# 4-storage.net
KiCad netlist of a schematic drawn in Altium Designer
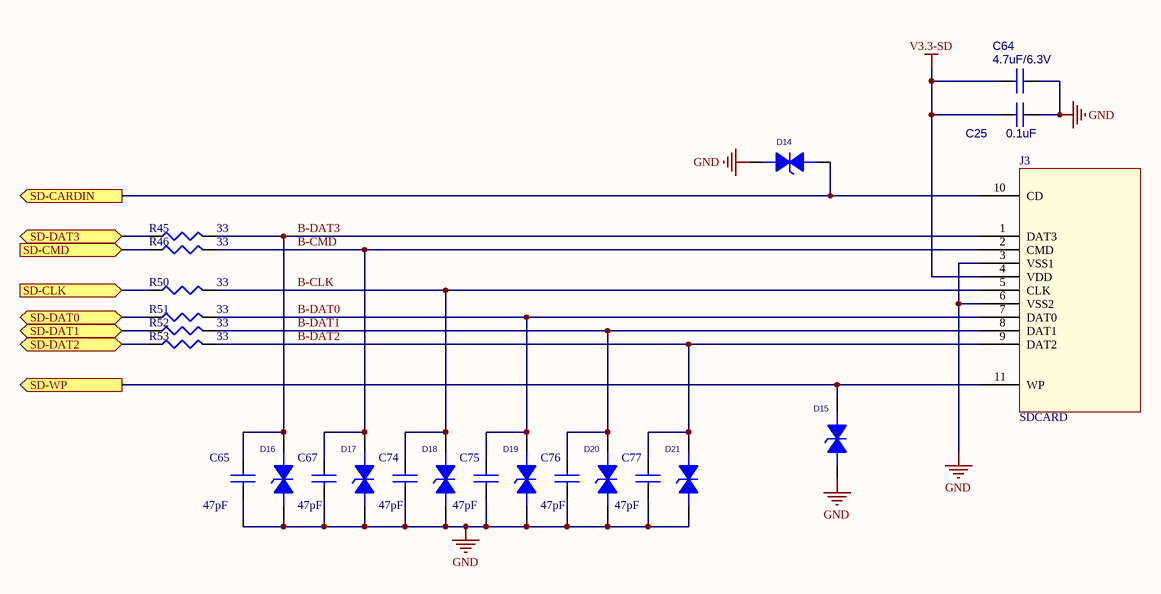
[diagram p0: 4-storage.SchDoc]

(export (version "E")
  (design (tool "Eeschema 10.0.6"))
  (components
    (comp (ref "C25") (value "0.1uF") (footprint "0603") (libsource (lib "*") (part "CAP NP_Dup2")))
    (comp (ref "C64") (value "4.7uF/6.3V") (footprint "0805") (libsource (lib "*") (part "CAP NP_Dup2")))
    (comp (ref "C65") (value "47pF") (libsource (lib "*") (part "CAP NP_Dup2")))
    (comp (ref "C67") (value "47pF") (libsource (lib "*") (part "CAP NP_Dup2")))
    (comp (ref "C74") (value "47pF") (libsource (lib "*") (part "CAP NP_Dup2")))
    (comp (ref "C75") (value "47pF") (libsource (lib "*") (part "CAP NP_Dup2")))
    (comp (ref "C76") (value "47pF") (libsource (lib "*") (part "CAP NP_Dup2")))
    (comp (ref "C77") (value "47pF") (libsource (lib "*") (part "CAP NP_Dup2")))
    (comp (ref "D14") (value "SMV0402G5R6N121T") (footprint "0402") (libsource (lib "*") (part "PESD")))
    (comp (ref "D15") (value "SMV0402G5R6N121T") (footprint "0402") (libsource (lib "*") (part "PESD")))
    (comp (ref "D16") (value "SMV0402G5R6N121T") (footprint "0402") (libsource (lib "*") (part "PESD")))
    (comp (ref "D17") (value "SMV0402G5R6N121T") (footprint "0402") (libsource (lib "*") (part "PESD")))
    (comp (ref "D18") (value "SMV0402G5R6N121T") (footprint "0402") (libsource (lib "*") (part "PESD")))
    (comp (ref "D19") (value "SMV0402G5R6N121T") (footprint "0402") (libsource (lib "*") (part "PESD")))
    (comp (ref "D20") (value "SMV0402G5R6N121T") (footprint "0402") (libsource (lib "*") (part "PESD")))
    (comp (ref "D21") (value "SMV0402G5R6N121T") (footprint "0402") (libsource (lib "*") (part "PESD")))
    (comp (ref "J3") (value "SDCARD") (footprint "SDCARD") (libsource (lib "Schlib") (part "SDCARD")))
    (comp (ref "R45") (value "33") (footprint "0603") (libsource (lib "*") (part "CR16-1003FM")))
    (comp (ref "R46") (value "33") (footprint "0603") (libsource (lib "*") (part "CR16-1003FM")))
    (comp (ref "R50") (value "33") (footprint "0603") (libsource (lib "*") (part "CR16-1003FM")))
    (comp (ref "R51") (value "33") (footprint "0603") (libsource (lib "*") (part "CR16-1003FM")))
    (comp (ref "R52") (value "33") (footprint "0603") (libsource (lib "*") (part "CR16-1003FM")))
    (comp (ref "R53") (value "33") (footprint "0603") (libsource (lib "*") (part "CR16-1003FM")))
  )
  (nets
    (net (code "1") (name "/B-CLK") (class "Default")
      (node (ref "C74") (pin "1") (pinfunction "1_1") (pintype "passive"))
      (node (ref "D18") (pin "2") (pinfunction "2_2") (pintype "passive"))
      (node (ref "J3") (pin "5") (pinfunction "CLK_5") (pintype "passive"))
      (node (ref "R50") (pin "2") (pinfunction "2_2") (pintype "passive"))
    )
    (net (code "2") (name "/B-CMD") (class "Default")
      (node (ref "C67") (pin "1") (pinfunction "1_1") (pintype "passive"))
      (node (ref "D17") (pin "2") (pinfunction "2_2") (pintype "passive"))
      (node (ref "J3") (pin "2") (pinfunction "CMD_2") (pintype "passive"))
      (node (ref "R46") (pin "2") (pinfunction "2_2") (pintype "passive"))
    )
    (net (code "3") (name "/B-DAT0") (class "Default")
      (node (ref "C75") (pin "1") (pinfunction "1_1") (pintype "passive"))
      (node (ref "D19") (pin "2") (pinfunction "2_2") (pintype "passive"))
      (node (ref "J3") (pin "7") (pinfunction "DAT0_7") (pintype "passive"))
      (node (ref "R51") (pin "2") (pinfunction "2_2") (pintype "passive"))
    )
    (net (code "4") (name "/B-DAT1") (class "Default")
      (node (ref "C76") (pin "1") (pinfunction "1_1") (pintype "passive"))
      (node (ref "D20") (pin "2") (pinfunction "2_2") (pintype "passive"))
      (node (ref "J3") (pin "8") (pinfunction "DAT1_8") (pintype "passive"))
      (node (ref "R52") (pin "2") (pinfunction "2_2") (pintype "passive"))
    )
    (net (code "5") (name "/B-DAT2") (class "Default")
      (node (ref "C77") (pin "1") (pinfunction "1_1") (pintype "passive"))
      (node (ref "D21") (pin "2") (pinfunction "2_2") (pintype "passive"))
      (node (ref "J3") (pin "9") (pinfunction "DAT2_9") (pintype "passive"))
      (node (ref "R53") (pin "2") (pinfunction "2_2") (pintype "passive"))
    )
    (net (code "6") (name "/B-DAT3") (class "Default")
      (node (ref "C65") (pin "1") (pinfunction "1_1") (pintype "passive"))
      (node (ref "D16") (pin "2") (pinfunction "2_2") (pintype "passive"))
      (node (ref "J3") (pin "1") (pinfunction "DAT3_1") (pintype "passive"))
      (node (ref "R45") (pin "2") (pinfunction "2_2") (pintype "passive"))
    )
    (net (code "7") (name "/SD-CARDIN") (class "Default")
      (node (ref "D14") (pin "1") (pinfunction "1_1") (pintype "passive"))
      (node (ref "J3") (pin "10") (pinfunction "CD_10") (pintype "passive"))
    )
    (net (code "8") (name "/SD-CLK") (class "Default")
      (node (ref "R50") (pin "1") (pinfunction "1_1") (pintype "passive"))
    )
    (net (code "9") (name "/SD-CMD") (class "Default")
      (node (ref "R46") (pin "1") (pinfunction "1_1") (pintype "passive"))
    )
    (net (code "10") (name "/SD-DAT0") (class "Default")
      (node (ref "R51") (pin "1") (pinfunction "1_1") (pintype "passive"))
    )
    (net (code "11") (name "/SD-DAT1") (class "Default")
      (node (ref "R52") (pin "1") (pinfunction "1_1") (pintype "passive"))
    )
    (net (code "12") (name "/SD-DAT2") (class "Default")
      (node (ref "R53") (pin "1") (pinfunction "1_1") (pintype "passive"))
    )
    (net (code "13") (name "/SD-DAT3") (class "Default")
      (node (ref "R45") (pin "1") (pinfunction "1_1") (pintype "passive"))
    )
    (net (code "14") (name "/SD-WP") (class "Default")
      (node (ref "D15") (pin "2") (pinfunction "2_2") (pintype "passive"))
      (node (ref "J3") (pin "11") (pinfunction "WP_11") (pintype "passive"))
    )
    (net (code "15") (name "GND") (class "Default")
      (node (ref "C25") (pin "1") (pinfunction "1_1") (pintype "passive"))
      (node (ref "C64") (pin "1") (pinfunction "1_1") (pintype "passive"))
      (node (ref "C65") (pin "2") (pinfunction "2_2") (pintype "passive"))
      (node (ref "C67") (pin "2") (pinfunction "2_2") (pintype "passive"))
      (node (ref "C74") (pin "2") (pinfunction "2_2") (pintype "passive"))
      (node (ref "C75") (pin "2") (pinfunction "2_2") (pintype "passive"))
      (node (ref "C76") (pin "2") (pinfunction "2_2") (pintype "passive"))
      (node (ref "C77") (pin "2") (pinfunction "2_2") (pintype "passive"))
      (node (ref "D14") (pin "2") (pinfunction "2_2") (pintype "passive"))
      (node (ref "D15") (pin "1") (pinfunction "1_1") (pintype "passive"))
      (node (ref "D16") (pin "1") (pinfunction "1_1") (pintype "passive"))
      (node (ref "D17") (pin "1") (pinfunction "1_1") (pintype "passive"))
      (node (ref "D18") (pin "1") (pinfunction "1_1") (pintype "passive"))
      (node (ref "D19") (pin "1") (pinfunction "1_1") (pintype "passive"))
      (node (ref "D20") (pin "1") (pinfunction "1_1") (pintype "passive"))
      (node (ref "D21") (pin "1") (pinfunction "1_1") (pintype "passive"))
      (node (ref "J3") (pin "3") (pinfunction "VSS1_3") (pintype "passive"))
      (node (ref "J3") (pin "6") (pinfunction "VSS2_6") (pintype "passive"))
    )
    (net (code "16") (name "V3.3-SD") (class "Default")
      (node (ref "C25") (pin "2") (pinfunction "2_2") (pintype "passive"))
      (node (ref "C64") (pin "2") (pinfunction "2_2") (pintype "passive"))
      (node (ref "J3") (pin "4") (pinfunction "VDD_4") (pintype "passive"))
    )
  )
)
